# PowerSupply.net
KiCad netlist of a schematic drawn in Altium Designer
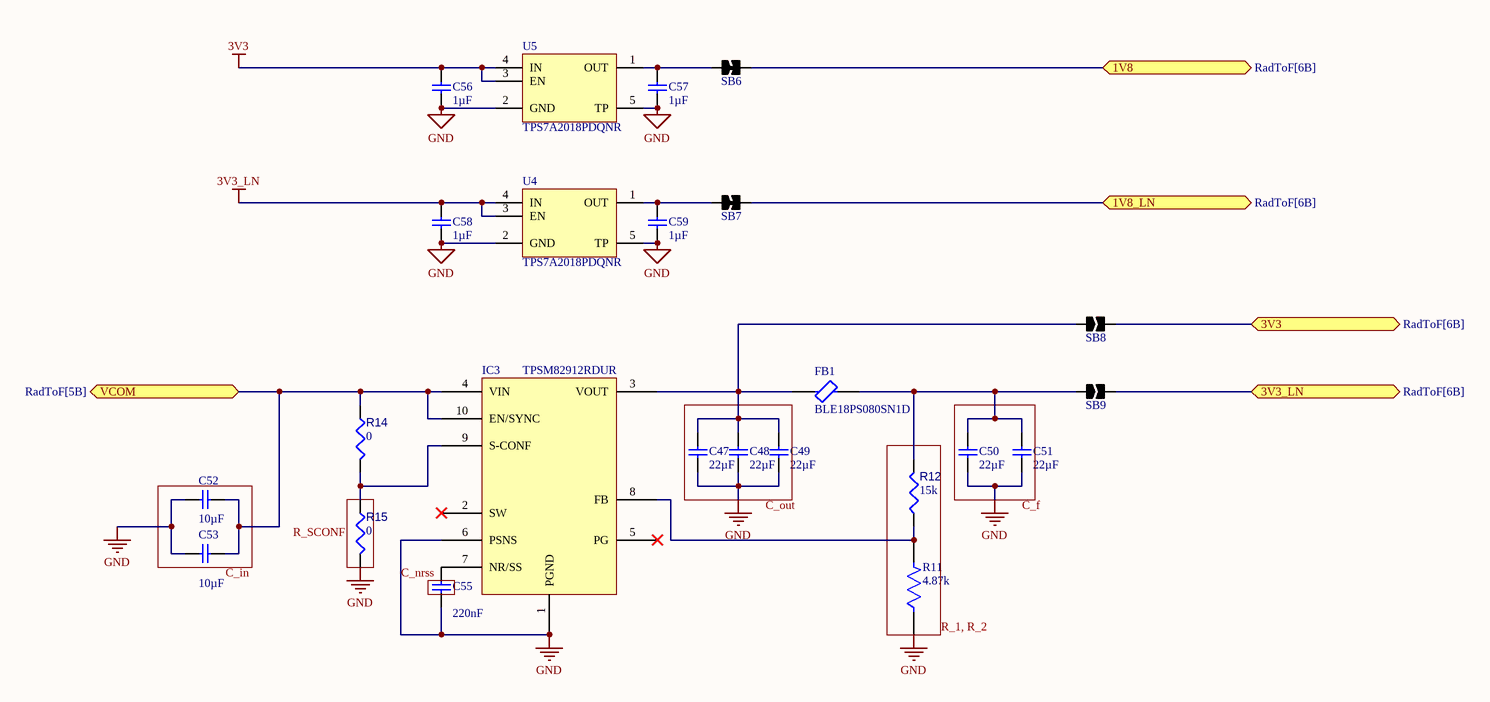
[diagram p0: PowerSupply.SchDoc]

(export (version "E")
  (design (tool "Eeschema 10.0.6"))
  (components
    (comp (ref "C47")
      (value "22µF")
      (footprint "CAP0402")
      (description "CAP CER 22uF 6.3V X5R 0402")
      (fields
        (field (name "TOLERANCE") "5%")
        (field (name "MANUFACTURER PART NUMBER") "GRM155R71H103KA88D")
        (field (name "SOURCE") "schuluka.SchLib")
      )
      (libsource (lib "Patrick Hupertz") (part "C_GRT033C80J224KE01D"))
    )
    (comp (ref "C48")
      (value "22µF")
      (footprint "CAP0402")
      (description "CAP CER 22uF 6.3V X5R 0402")
      (fields
        (field (name "TOLERANCE") "5%")
        (field (name "MANUFACTURER PART NUMBER") "GRM155R71H103KA88D")
        (field (name "SOURCE") "schuluka.SchLib")
      )
      (libsource (lib "Patrick Hupertz") (part "C_GRT033C80J224KE01D"))
    )
    (comp (ref "C49")
      (value "22µF")
      (footprint "CAP0402")
      (description "CAP CER 22uF 6.3V X5R 0402")
      (fields
        (field (name "TOLERANCE") "5%")
        (field (name "MANUFACTURER PART NUMBER") "GRM155R71H103KA88D")
        (field (name "SOURCE") "schuluka.SchLib")
      )
      (libsource (lib "Patrick Hupertz") (part "C_GRT033C80J224KE01D"))
    )
    (comp (ref "C50")
      (value "22µF")
      (footprint "CAP0402")
      (description "CAP CER 22uF 6.3V X5R 0402")
      (fields
        (field (name "TOLERANCE") "5%")
        (field (name "MANUFACTURER PART NUMBER") "GRM155R71H103KA88D")
        (field (name "SOURCE") "schuluka.SchLib")
      )
      (libsource (lib "Patrick Hupertz") (part "C_GRT033C80J224KE01D"))
    )
    (comp (ref "C51")
      (value "22µF")
      (footprint "CAP0402")
      (description "CAP CER 22uF 6.3V X5R 0402")
      (fields
        (field (name "TOLERANCE") "5%")
        (field (name "MANUFACTURER PART NUMBER") "GRM155R71H103KA88D")
        (field (name "SOURCE") "schuluka.SchLib")
      )
      (libsource (lib "Patrick Hupertz") (part "C_GRT033C80J224KE01D"))
    )
    (comp (ref "C52")
      (value "10µF")
      (footprint "CAP0402")
      (description "CAP CER  10uF 10V X5R 20% 0402")
      (fields
        (field (name "MANUFACTURER") "Murata Electronics")
        (field (name "TOLERANCE") "5%")
        (field (name "SOURCE") "schuluka.SchLib")
      )
      (libsource (lib "Patrick Hupertz") (part "C_GRT033C80J224KE01D"))
    )
    (comp (ref "C53")
      (value "10µF")
      (footprint "CAP0402")
      (description "CAP CER  10uF 10V X5R 20% 0402")
      (fields
        (field (name "MANUFACTURER") "Murata Electronics")
        (field (name "TOLERANCE") "5%")
        (field (name "SOURCE") "schuluka.SchLib")
      )
      (libsource (lib "Patrick Hupertz") (part "C_GRT033C80J224KE01D"))
    )
    (comp (ref "C55")
      (value "220nF")
      (footprint "CAP0201")
      (description "CAP CER 0.22uF 6.3V X6S 0201")
      (fields
        (field (name "TOLERANCE") "10%")
        (field (name "MANUFACTURER") "Murata Electronics")
        (field (name "SOURCE") "schuluka.SchLib")
      )
      (libsource (lib "Patrick Hupertz") (part "C_GRT033C80J224KE01D"))
    )
    (comp (ref "C56")
      (value "1µF")
      (footprint "CAP0402")
      (description "CAP CER 1uF 25V X5R 0402")
      (fields
        (field (name "MANUFACTURER PART NUMBER") "GRM033R61A105ME15D")
        (field (name "MANUFACTURER") "Murata")
        (field (name "SOURCE") "schuluka.SchLib")
      )
      (libsource (lib "Patrick Hupertz") (part "C_GRT033C80J224KE01D"))
    )
    (comp (ref "C57")
      (value "1µF")
      (footprint "CAP0402")
      (description "CAP CER 1uF 25V X5R 0402")
      (fields
        (field (name "MANUFACTURER PART NUMBER") "GRM033R61A105ME15D")
        (field (name "MANUFACTURER") "Murata")
        (field (name "SOURCE") "schuluka.SchLib")
      )
      (libsource (lib "Patrick Hupertz") (part "C_GRT033C80J224KE01D"))
    )
    (comp (ref "C58")
      (value "1µF")
      (footprint "CAP0402")
      (description "CAP CER 1uF 25V X5R 0402")
      (fields
        (field (name "MANUFACTURER PART NUMBER") "GRM033R61A105ME15D")
        (field (name "MANUFACTURER") "Murata")
        (field (name "SOURCE") "schuluka.SchLib")
      )
      (libsource (lib "Patrick Hupertz") (part "C_GRT033C80J224KE01D"))
    )
    (comp (ref "C59")
      (value "1µF")
      (footprint "CAP0402")
      (description "CAP CER 1uF 25V X5R 0402")
      (fields
        (field (name "MANUFACTURER PART NUMBER") "GRM033R61A105ME15D")
        (field (name "MANUFACTURER") "Murata")
        (field (name "SOURCE") "schuluka.SchLib")
      )
      (libsource (lib "Patrick Hupertz") (part "C_GRT033C80J224KE01D"))
    )
    (comp (ref "FB1")
      (value "BLE18PS080SN1D")
      (footprint "FP-BLE18-0_15-t0_6-IPC_B")
      (description "Ferrite Chip Bead 8A 8.5Ohm 2-Pin 0603 Paper T/R")
      (libsource (lib "Altium Content Vault") (part "5f30dd21d616792df468990f7003faa"))
    )
    (comp (ref "IC3")
      (value "TPSM82912RDUR")
      (footprint "TPSM82912RDUR")
      (libsource (lib "SchlibPH") (part "TPSM82912RDUR"))
    )
    (comp (ref "R11")
      (value "4.87k")
      (footprint "FP-RG1005-IPC_C")
      (description "Automotive Metal Thin Film Chip Resistor, 0402, 4.87kΩ, 0.1%, 25ppm/°C, 0.0625W, 75V")
      (fields (field (name "TOLERANCE") "0.1%"))
      (libsource (lib "Altium Content Vault") (part "1029c3af85768c4190bb7ad29bc67b5"))
    )
    (comp (ref "R12")
      (value "15k")
      (footprint "RESC1005X40X25ML10T10")
      (description "Chip Resistor, 15 KOhm, +/- 1%, 0.063 W, -55 to 155 degC, 0402 (1005 Metric)")
      (fields (field (name "POWER") "63mW") (field (name "TOLERANCE") "1%"))
      (libsource (lib "Patrick Hupertz") (part "RES-2"))
    )
    (comp (ref "R14")
      (value "0")
      (footprint "RESC0402(1005)_L")
      (description "Jumper 0402")
      (libsource (lib "Patrick Hupertz") (part "RES-2"))
    )
    (comp (ref "R15")
      (value "0")
      (footprint "RESC0402(1005)_L")
      (description "Jumper 0402")
      (libsource (lib "Patrick Hupertz") (part "RES-2"))
    )
    (comp (ref "SB6")
      (value "SB2_0402_close")
      (footprint "SB2_0402_CLOSE")
      (description "Custom Solder jumper, closed")
      (libsource (lib "SchlibPH") (part "JUMP_SB2_0402_close"))
    )
    (comp (ref "SB7")
      (value "SB2_0402_close")
      (footprint "SB2_0402_CLOSE")
      (description "Custom Solder jumper, closed")
      (libsource (lib "SchlibPH") (part "JUMP_SB2_0402_close"))
    )
    (comp (ref "SB8")
      (value "SB2_0402")
      (footprint "SB2_0402")
      (description "Custom Solder jumper, open")
      (libsource (lib "SchlibPH") (part "JUMP_SB2_0402"))
    )
    (comp (ref "SB9")
      (value "SB2_0402")
      (footprint "SB2_0402")
      (description "Custom Solder jumper, open")
      (libsource (lib "SchlibPH") (part "JUMP_SB2_0402"))
    )
    (comp (ref "U4")
      (value "TPS7A2018PDQNR")
      (footprint "DQN0004A_V")
      (description "1.8V 300-mA ultra-low-noise low-IQ low-dropout (LDO) linear regulator with high PSRR")
      (fields (field (name "MANUFACTURER") "Texas Instruments"))
      (libsource (lib "SchlibPH") (part "LDO_TPS7A2018PDQNR"))
    )
    (comp (ref "U5")
      (value "TPS7A2018PDQNR")
      (footprint "DQN0004A_V")
      (description "1.8V 300-mA ultra-low-noise low-IQ low-dropout (LDO) linear regulator with high PSRR")
      (fields (field (name "MANUFACTURER") "Texas Instruments"))
      (libsource (lib "SchlibPH") (part "LDO_TPS7A2018PDQNR"))
    )
  )
  (nets
    (net (code "1") (name "/1V8") (class "Default")
      (node (ref "SB6") (pin "1") (pinfunction "1_1") (pintype "passive"))
    )
    (net (code "2") (name "/1V8_LN") (class "Default")
      (node (ref "SB7") (pin "1") (pinfunction "1_1") (pintype "passive"))
    )
    (net (code "3") (name "/VCOM") (class "Default")
      (node (ref "C52") (pin "2") (pinfunction "2_2") (pintype "passive"))
      (node (ref "C53") (pin "2") (pinfunction "2_2") (pintype "passive"))
      (node (ref "IC3") (pin "10") (pinfunction "EN/SYNC_10") (pintype "passive"))
      (node (ref "IC3") (pin "4") (pinfunction "VIN_4") (pintype "passive"))
      (node (ref "R14") (pin "1") (pinfunction "1_1") (pintype "passive"))
    )
    (net (code "4") (name "3V3") (class "Default")
      (node (ref "C56") (pin "2") (pinfunction "2_2") (pintype "passive"))
      (node (ref "SB8") (pin "1") (pinfunction "1_1") (pintype "passive"))
      (node (ref "U5") (pin "3") (pinfunction "EN_3") (pintype "passive"))
      (node (ref "U5") (pin "4") (pinfunction "IN_4") (pintype "passive"))
    )
    (net (code "5") (name "3V3_LN") (class "Default")
      (node (ref "C58") (pin "2") (pinfunction "2_2") (pintype "passive"))
      (node (ref "SB9") (pin "1") (pinfunction "1_1") (pintype "passive"))
      (node (ref "U4") (pin "3") (pinfunction "EN_3") (pintype "passive"))
      (node (ref "U4") (pin "4") (pinfunction "IN_4") (pintype "passive"))
    )
    (net (code "6") (name "GND") (class "Default")
      (node (ref "C47") (pin "1") (pinfunction "1_1") (pintype "passive"))
      (node (ref "C48") (pin "1") (pinfunction "1_1") (pintype "passive"))
      (node (ref "C49") (pin "1") (pinfunction "1_1") (pintype "passive"))
      (node (ref "C50") (pin "1") (pinfunction "1_1") (pintype "passive"))
      (node (ref "C51") (pin "1") (pinfunction "1_1") (pintype "passive"))
      (node (ref "C52") (pin "1") (pinfunction "1_1") (pintype "passive"))
      (node (ref "C53") (pin "1") (pinfunction "1_1") (pintype "passive"))
      (node (ref "C55") (pin "1") (pinfunction "1_1") (pintype "passive"))
      (node (ref "C56") (pin "1") (pinfunction "1_1") (pintype "passive"))
      (node (ref "C57") (pin "1") (pinfunction "1_1") (pintype "passive"))
      (node (ref "C58") (pin "1") (pinfunction "1_1") (pintype "passive"))
      (node (ref "C59") (pin "1") (pinfunction "1_1") (pintype "passive"))
      (node (ref "IC3") (pin "1") (pinfunction "PGND_1") (pintype "passive"))
      (node (ref "IC3") (pin "6") (pinfunction "PSNS_6") (pintype "passive"))
      (node (ref "R11") (pin "1") (pinfunction "1_1") (pintype "passive"))
      (node (ref "R15") (pin "2") (pinfunction "2_2") (pintype "passive"))
      (node (ref "U4") (pin "2") (pinfunction "GND_2") (pintype "passive"))
      (node (ref "U4") (pin "5") (pinfunction "TP_5") (pintype "passive"))
      (node (ref "U5") (pin "2") (pinfunction "GND_2") (pintype "passive"))
      (node (ref "U5") (pin "5") (pinfunction "TP_5") (pintype "passive"))
    )
    (net (code "7") (name "Net-(C50-Pad2)") (class "Default")
      (node (ref "C50") (pin "2") (pinfunction "2_2") (pintype "passive"))
      (node (ref "C51") (pin "2") (pinfunction "2_2") (pintype "passive"))
      (node (ref "FB1") (pin "2") (pinfunction "2_2") (pintype "passive"))
      (node (ref "R12") (pin "2") (pinfunction "2_2") (pintype "passive"))
      (node (ref "SB9") (pin "2") (pinfunction "2_2") (pintype "passive"))
    )
    (net (code "8") (name "Net-(IC3-FB)") (class "Default")
      (node (ref "IC3") (pin "8") (pinfunction "FB_8") (pintype "passive"))
      (node (ref "R11") (pin "2") (pinfunction "2_2") (pintype "passive"))
      (node (ref "R12") (pin "1") (pinfunction "1_1") (pintype "passive"))
    )
    (net (code "9") (name "Net-(IC3-NR{slash}SS)") (class "Default")
      (node (ref "C55") (pin "2") (pinfunction "2_2") (pintype "passive"))
      (node (ref "IC3") (pin "7") (pinfunction "NR/SS_7") (pintype "passive"))
    )
    (net (code "10") (name "Net-(IC3-S-CONF)") (class "Default")
      (node (ref "IC3") (pin "9") (pinfunction "S-CONF_9") (pintype "passive"))
      (node (ref "R14") (pin "2") (pinfunction "2_2") (pintype "passive"))
      (node (ref "R15") (pin "1") (pinfunction "1_1") (pintype "passive"))
    )
    (net (code "11") (name "Net-(IC3-VOUT)") (class "Default")
      (node (ref "C47") (pin "2") (pinfunction "2_2") (pintype "passive"))
      (node (ref "C48") (pin "2") (pinfunction "2_2") (pintype "passive"))
      (node (ref "C49") (pin "2") (pinfunction "2_2") (pintype "passive"))
      (node (ref "FB1") (pin "1") (pinfunction "1_1") (pintype "passive"))
      (node (ref "IC3") (pin "3") (pinfunction "VOUT_3") (pintype "passive"))
      (node (ref "SB8") (pin "2") (pinfunction "2_2") (pintype "passive"))
    )
    (net (code "12") (name "Net-(U4-OUT)") (class "Default")
      (node (ref "C59") (pin "2") (pinfunction "2_2") (pintype "passive"))
      (node (ref "SB7") (pin "2") (pinfunction "2_2") (pintype "passive"))
      (node (ref "U4") (pin "1") (pinfunction "OUT_1") (pintype "passive"))
    )
    (net (code "13") (name "Net-(U5-OUT)") (class "Default")
      (node (ref "C57") (pin "2") (pinfunction "2_2") (pintype "passive"))
      (node (ref "SB6") (pin "2") (pinfunction "2_2") (pintype "passive"))
      (node (ref "U5") (pin "1") (pinfunction "OUT_1") (pintype "passive"))
    )
    (net (code "14") (name "unconnected-(IC3-PG-Pad5)") (class "Default")
      (node (ref "IC3") (pin "5") (pinfunction "PG_5") (pintype "passive+no_connect"))
    )
    (net (code "15") (name "unconnected-(IC3-SW-Pad2)") (class "Default")
      (node (ref "IC3") (pin "2") (pinfunction "SW_2") (pintype "passive+no_connect"))
    )
  )
)
